# RobotPCB.net
KiCad netlist of a schematic drawn in EAGLE
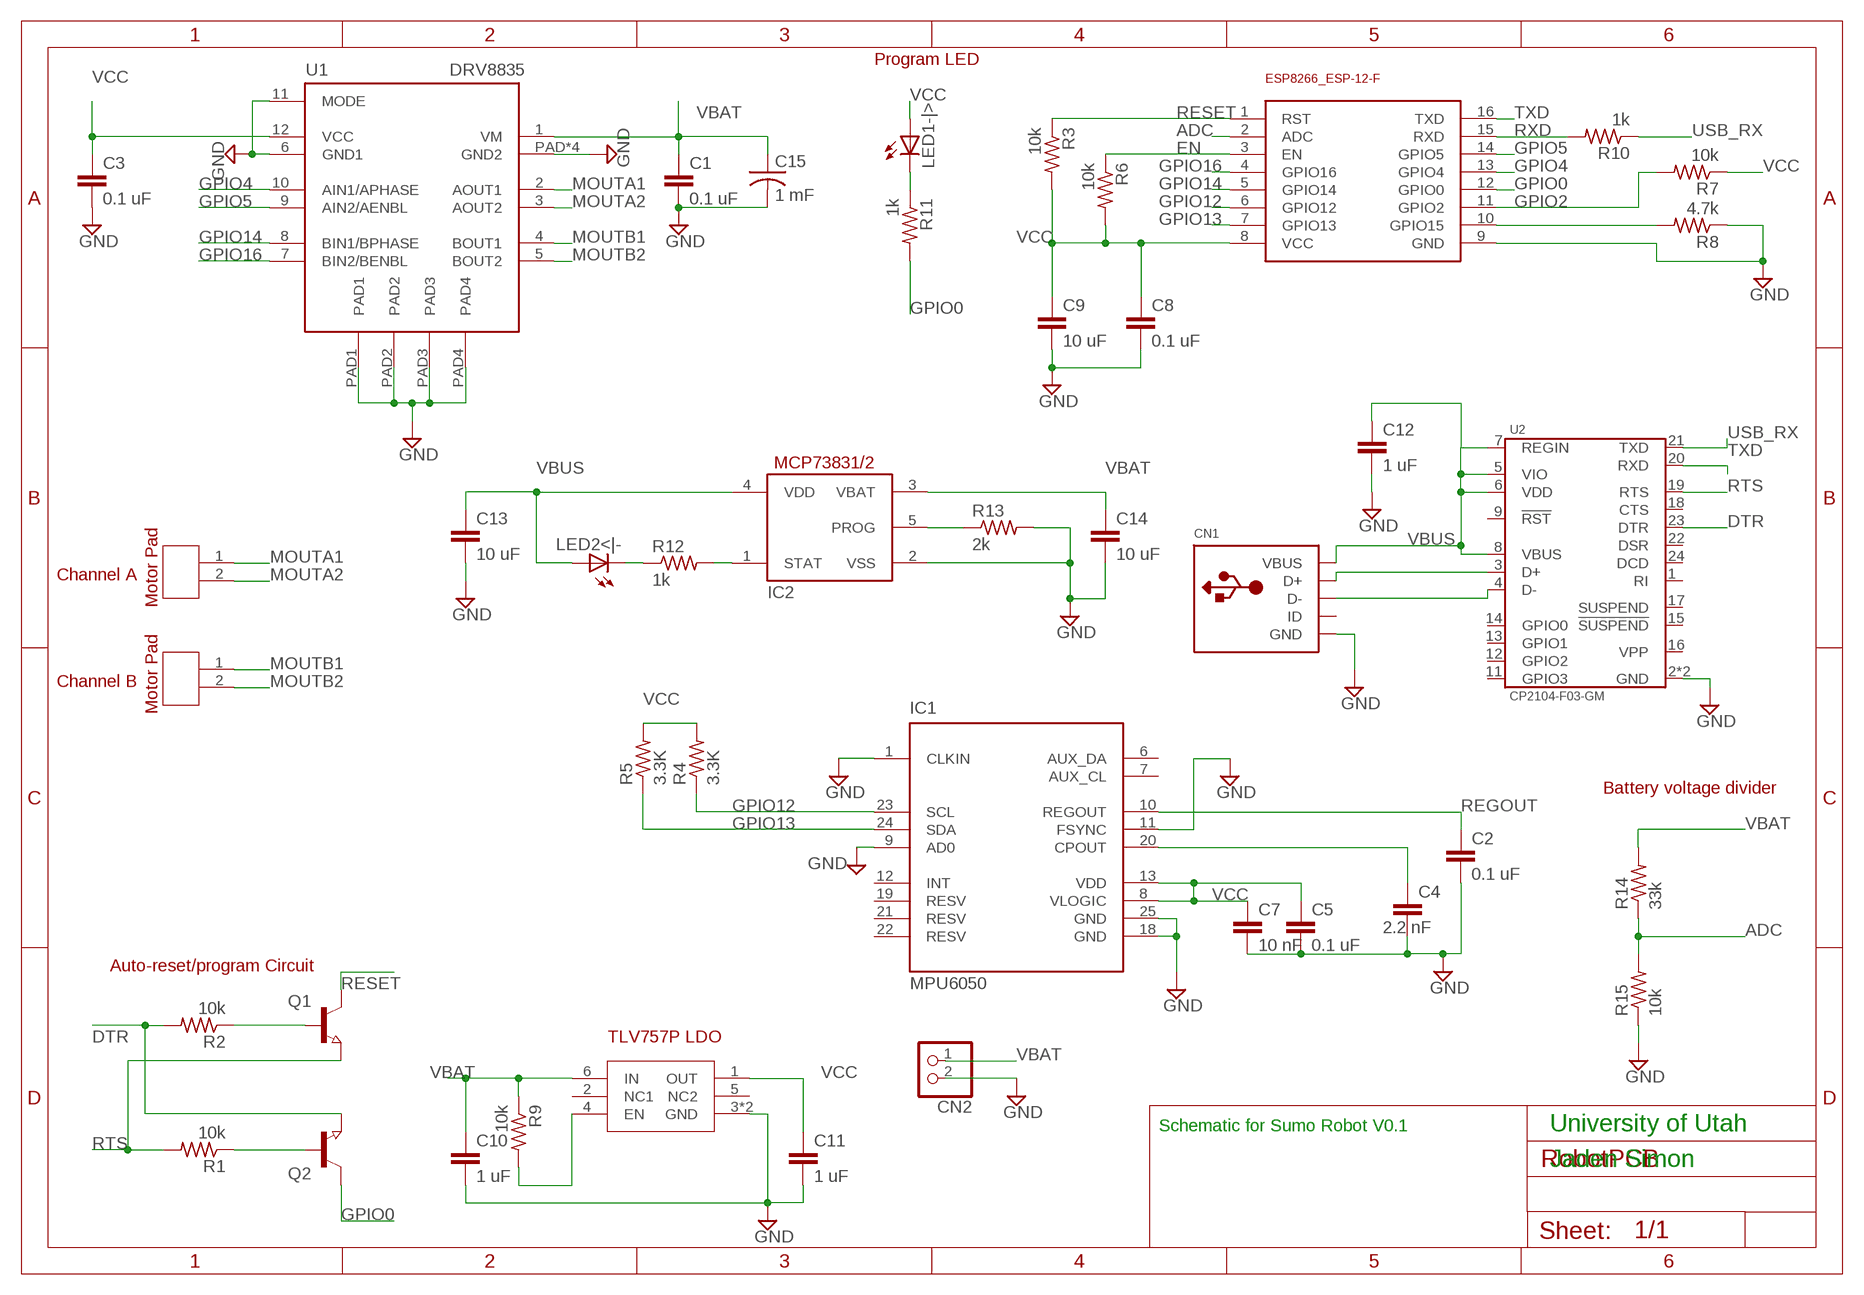
[diagram p0: schematic, sheet 1]

(export (version "E")
  (design (tool "Eeschema 10.0.6"))
  (components
    (comp (ref "C1")
      (value "0.1 uF")
      (footprint "eagle-import:C1206")
      (libsource (lib "eagle-import") (part "C-EUC1206"))
    )
    (comp (ref "C2")
      (value "0.1 uF")
      (footprint "eagle-import:C1206")
      (libsource (lib "eagle-import") (part "C-EUC1206"))
    )
    (comp (ref "C3")
      (value "0.1 uF")
      (footprint "eagle-import:C1206")
      (libsource (lib "eagle-import") (part "C-EUC1206"))
    )
    (comp (ref "C4")
      (value "2.2 nF")
      (footprint "eagle-import:C1206")
      (libsource (lib "eagle-import") (part "C-EUC1206"))
    )
    (comp (ref "C5")
      (value "0.1 uF")
      (footprint "eagle-import:C1206")
      (libsource (lib "eagle-import") (part "C-EUC1206"))
    )
    (comp (ref "C7")
      (value "10 nF")
      (footprint "eagle-import:C1206")
      (libsource (lib "eagle-import") (part "C-EUC1206"))
    )
    (comp (ref "C8")
      (value "0.1 uF")
      (footprint "eagle-import:C1206")
      (libsource (lib "eagle-import") (part "C-EUC1206"))
    )
    (comp (ref "C9")
      (value "10 uF")
      (footprint "eagle-import:C1206")
      (libsource (lib "eagle-import") (part "C-EUC1206"))
    )
    (comp (ref "C10")
      (value "1 uF")
      (footprint "eagle-import:C1206")
      (libsource (lib "eagle-import") (part "C-EUC1206"))
    )
    (comp (ref "C11")
      (value "1 uF")
      (footprint "eagle-import:C1206")
      (libsource (lib "eagle-import") (part "C-EUC1206"))
    )
    (comp (ref "C12")
      (value "1 uF")
      (footprint "eagle-import:C1206")
      (libsource (lib "eagle-import") (part "C-EUC1206"))
    )
    (comp (ref "C13")
      (value "10 uF")
      (footprint "eagle-import:C1206")
      (libsource (lib "eagle-import") (part "C-EUC1206"))
    )
    (comp (ref "C14")
      (value "10 uF")
      (footprint "eagle-import:C1206")
      (libsource (lib "eagle-import") (part "C-EUC1206"))
    )
    (comp (ref "C15")
      (value "1 mF")
      (footprint "eagle-import:C050-075X075")
      (libsource (lib "eagle-import") (part "C-US050-075X075"))
    )
    (comp (ref "CN1")
      (value "USBMINIB")
      (footprint "eagle-import:USB-MINIB")
      (libsource (lib "eagle-import") (part "USBMINIB"))
    )
    (comp (ref "CN2")
      (value "JST_2PIN-THM")
      (footprint "eagle-import:JST-PH-2-THM")
      (libsource (lib "eagle-import") (part "JST_2PIN-THM"))
    )
    (comp (ref "IC1")
      (value "MPU6050")
      (footprint "eagle-import:QFN50P400X400X95-25T265X275N")
      (libsource (lib "eagle-import") (part "MPU6050"))
    )
    (comp (ref "IC2")
      (value "MCP73831/OT")
      (footprint "eagle-import:SOT23-5L")
      (libsource (lib "eagle-import") (part "MCP73831/OT"))
    )
    (comp (ref "LED1-|>")
      (value "LEDSMT1206")
      (footprint "eagle-import:1206")
      (libsource (lib "eagle-import") (part "LEDSMT1206"))
    )
    (comp (ref "LED2<|-")
      (value "LEDSMT1206")
      (footprint "eagle-import:1206")
      (libsource (lib "eagle-import") (part "led_259_LEDSMT1206"))
    )
    (comp (ref "Q1")
      (value "NPN-TRANSISTOR_SOT23")
      (footprint "eagle-import:SOT23")
      (libsource (lib "eagle-import") (part "NPN-TRANSISTOR_SOT23"))
    )
    (comp (ref "Q2")
      (value "NPN-TRANSISTOR_SOT23")
      (footprint "eagle-import:SOT23")
      (libsource (lib "eagle-import") (part "NPN-TRANSISTOR_SOT23"))
    )
    (comp (ref "R1")
      (value "10k")
      (footprint "eagle-import:M1206")
      (libsource (lib "eagle-import") (part "R-US_M1206"))
    )
    (comp (ref "R2")
      (value "10k")
      (footprint "eagle-import:M1206")
      (libsource (lib "eagle-import") (part "R-US_M1206"))
    )
    (comp (ref "R3")
      (value "10k")
      (footprint "eagle-import:M1206")
      (libsource (lib "eagle-import") (part "R-US_M1206"))
    )
    (comp (ref "R4")
      (value "3.3K")
      (footprint "eagle-import:M1206")
      (libsource (lib "eagle-import") (part "R-US_M1206"))
    )
    (comp (ref "R5")
      (value "3.3K")
      (footprint "eagle-import:M1206")
      (libsource (lib "eagle-import") (part "R-US_M1206"))
    )
    (comp (ref "R6")
      (value "10k")
      (footprint "eagle-import:M1206")
      (libsource (lib "eagle-import") (part "R-US_M1206"))
    )
    (comp (ref "R7")
      (value "10k")
      (footprint "eagle-import:M1206")
      (libsource (lib "eagle-import") (part "R-US_M1206"))
    )
    (comp (ref "R8")
      (value "4.7k")
      (footprint "eagle-import:M1206")
      (libsource (lib "eagle-import") (part "R-US_M1206"))
    )
    (comp (ref "R9")
      (value "10k")
      (footprint "eagle-import:M1206")
      (libsource (lib "eagle-import") (part "R-US_M1206"))
    )
    (comp (ref "R10")
      (value "1k")
      (footprint "eagle-import:M1206")
      (libsource (lib "eagle-import") (part "R-US_M1206"))
    )
    (comp (ref "R11")
      (value "1k")
      (footprint "eagle-import:M1206")
      (libsource (lib "eagle-import") (part "R-US_M1206"))
    )
    (comp (ref "R12")
      (value "1k")
      (footprint "eagle-import:M1206")
      (libsource (lib "eagle-import") (part "R-US_M1206"))
    )
    (comp (ref "R13")
      (value "2k")
      (footprint "eagle-import:M1206")
      (libsource (lib "eagle-import") (part "R-US_M1206"))
    )
    (comp (ref "R14")
      (value "33k")
      (footprint "eagle-import:M1206")
      (libsource (lib "eagle-import") (part "R-US_M1206"))
    )
    (comp (ref "R15")
      (value "10k")
      (footprint "eagle-import:M1206")
      (libsource (lib "eagle-import") (part "R-US_M1206"))
    )
    (comp (ref "U$1")
      (value "ESP8266_ESP-12")
      (footprint "eagle-import:ESP8266-ESP12")
      (libsource (lib "eagle-import") (part "ESP8266_ESP-12"))
    )
    (comp (ref "U$2")
      (value "TLV757P")
      (footprint "eagle-import:WSON-6")
      (libsource (lib "eagle-import") (part "TLV757P"))
    )
    (comp (ref "U$3")
      (value "MOTOR_PAD")
      (footprint "eagle-import:MOTOR_PAD")
      (libsource (lib "eagle-import") (part "MOTOR_PAD"))
    )
    (comp (ref "U$4")
      (value "MOTOR_PAD")
      (footprint "eagle-import:MOTOR_PAD")
      (libsource (lib "eagle-import") (part "MOTOR_PAD"))
    )
    (comp (ref "U1")
      (value "DRV8835")
      (footprint "eagle-import:WSON_2X3")
      (libsource (lib "eagle-import") (part "DRV8835"))
    )
    (comp (ref "U2")
      (value "CP2104-F03-GM")
      (footprint "eagle-import:QFN-24-4X4")
      (libsource (lib "eagle-import") (part "CP2104-F03-GM"))
    )
  )
  (nets
    (net (code "1") (name "/ADC") (class "Default")
      (node (ref "R14") (pin "1") (pinfunction "1_1") (pintype "passive"))
      (node (ref "R15") (pin "2") (pinfunction "2_2") (pintype "passive"))
      (node (ref "U$1") (pin "2") (pinfunction "ADC_2") (pintype "bidirectional"))
    )
    (net (code "2") (name "/DTR") (class "Default")
      (node (ref "Q2") (pin "2") (pinfunction "E_2") (pintype "passive"))
      (node (ref "R2") (pin "2") (pinfunction "2_2") (pintype "passive"))
      (node (ref "U2") (pin "23") (pinfunction "DTR_23") (pintype "bidirectional"))
    )
    (net (code "3") (name "/EN") (class "Default")
      (node (ref "R6") (pin "1") (pinfunction "1_1") (pintype "passive"))
      (node (ref "U$1") (pin "3") (pinfunction "EN_3") (pintype "bidirectional"))
    )
    (net (code "4") (name "/GPIO0") (class "Default")
      (node (ref "Q2") (pin "3") (pinfunction "C_3") (pintype "passive"))
      (node (ref "R11") (pin "2") (pinfunction "2_2") (pintype "passive"))
      (node (ref "U$1") (pin "12") (pinfunction "GPIO0_12") (pintype "bidirectional"))
    )
    (net (code "5") (name "/GPIO2") (class "Default")
      (node (ref "R7") (pin "2") (pinfunction "2_2") (pintype "passive"))
      (node (ref "U$1") (pin "11") (pinfunction "GPIO2_11") (pintype "bidirectional"))
    )
    (net (code "6") (name "/GPIO4") (class "Default")
      (node (ref "U$1") (pin "13") (pinfunction "GPIO4_13") (pintype "bidirectional"))
      (node (ref "U1") (pin "10") (pinfunction "AIN1/APHASE_10") (pintype "bidirectional"))
    )
    (net (code "7") (name "/GPIO5") (class "Default")
      (node (ref "U$1") (pin "14") (pinfunction "GPIO5_14") (pintype "bidirectional"))
      (node (ref "U1") (pin "9") (pinfunction "AIN2/AENBL_9") (pintype "bidirectional"))
    )
    (net (code "8") (name "/GPIO12") (class "Default")
      (node (ref "IC1") (pin "23") (pinfunction "SCL_23") (pintype "input"))
      (node (ref "R4") (pin "1") (pinfunction "1_1") (pintype "passive"))
      (node (ref "U$1") (pin "6") (pinfunction "GPIO12_6") (pintype "bidirectional"))
    )
    (net (code "9") (name "/GPIO13") (class "Default")
      (node (ref "IC1") (pin "24") (pinfunction "SDA_24") (pintype "bidirectional"))
      (node (ref "R5") (pin "1") (pinfunction "1_1") (pintype "passive"))
      (node (ref "U$1") (pin "7") (pinfunction "GPIO13_7") (pintype "bidirectional"))
    )
    (net (code "10") (name "/GPIO14") (class "Default")
      (node (ref "U$1") (pin "5") (pinfunction "GPIO14_5") (pintype "bidirectional"))
      (node (ref "U1") (pin "8") (pinfunction "BIN1/BPHASE_8") (pintype "bidirectional"))
    )
    (net (code "11") (name "/GPIO16") (class "Default")
      (node (ref "U$1") (pin "4") (pinfunction "GPIO16_4") (pintype "bidirectional"))
      (node (ref "U1") (pin "7") (pinfunction "BIN2/BENBL_7") (pintype "bidirectional"))
    )
    (net (code "12") (name "/MOUTA1") (class "Default")
      (node (ref "U$3") (pin "1") (pinfunction "L_1") (pintype "input"))
      (node (ref "U1") (pin "2") (pinfunction "AOUT1_2") (pintype "bidirectional"))
    )
    (net (code "13") (name "/MOUTA2") (class "Default")
      (node (ref "U$3") (pin "2") (pinfunction "2_2") (pintype "input"))
      (node (ref "U1") (pin "3") (pinfunction "AOUT2_3") (pintype "bidirectional"))
    )
    (net (code "14") (name "/MOUTB1") (class "Default")
      (node (ref "U$4") (pin "1") (pinfunction "L_1") (pintype "input"))
      (node (ref "U1") (pin "4") (pinfunction "BOUT1_4") (pintype "bidirectional"))
    )
    (net (code "15") (name "/MOUTB2") (class "Default")
      (node (ref "U$4") (pin "2") (pinfunction "2_2") (pintype "input"))
      (node (ref "U1") (pin "5") (pinfunction "BOUT2_5") (pintype "bidirectional"))
    )
    (net (code "16") (name "/REGOUT") (class "Default")
      (node (ref "C2") (pin "1") (pinfunction "1_1") (pintype "passive"))
      (node (ref "IC1") (pin "10") (pinfunction "REGOUT_10") (pintype "output"))
    )
    (net (code "17") (name "/RESET") (class "Default")
      (node (ref "Q1") (pin "3") (pinfunction "C_3") (pintype "passive"))
      (node (ref "R3") (pin "1") (pinfunction "1_1") (pintype "passive"))
      (node (ref "U$1") (pin "1") (pinfunction "RST_1") (pintype "bidirectional"))
    )
    (net (code "18") (name "/RTS") (class "Default")
      (node (ref "Q1") (pin "2") (pinfunction "E_2") (pintype "passive"))
      (node (ref "R1") (pin "2") (pinfunction "2_2") (pintype "passive"))
      (node (ref "U2") (pin "19") (pinfunction "RTS_19") (pintype "bidirectional"))
    )
    (net (code "19") (name "/RXD") (class "Default")
      (node (ref "R10") (pin "2") (pinfunction "2_2") (pintype "passive"))
      (node (ref "U$1") (pin "15") (pinfunction "RXD_15") (pintype "bidirectional"))
    )
    (net (code "20") (name "/TXD") (class "Default")
      (node (ref "U$1") (pin "16") (pinfunction "TXD_16") (pintype "bidirectional"))
      (node (ref "U2") (pin "20") (pinfunction "RXD_20") (pintype "bidirectional"))
    )
    (net (code "21") (name "/USB_RX") (class "Default")
      (node (ref "R10") (pin "1") (pinfunction "1_1") (pintype "passive"))
      (node (ref "U2") (pin "21") (pinfunction "TXD_21") (pintype "bidirectional"))
    )
    (net (code "22") (name "/VBAT") (class "Default")
      (node (ref "C1") (pin "1") (pinfunction "1_1") (pintype "passive"))
      (node (ref "C10") (pin "1") (pinfunction "1_1") (pintype "passive"))
      (node (ref "C14") (pin "1") (pinfunction "1_1") (pintype "passive"))
      (node (ref "C15") (pin "1") (pinfunction "1_1") (pintype "passive"))
      (node (ref "CN2") (pin "1") (pinfunction "2_1") (pintype "passive"))
      (node (ref "IC2") (pin "3") (pinfunction "VBAT_3") (pintype "bidirectional"))
      (node (ref "R14") (pin "2") (pinfunction "2_2") (pintype "passive"))
      (node (ref "R9") (pin "1") (pinfunction "1_1") (pintype "passive"))
      (node (ref "U$2") (pin "6") (pinfunction "IN_6") (pintype "bidirectional"))
      (node (ref "U1") (pin "1") (pinfunction "VM_1") (pintype "bidirectional"))
    )
    (net (code "23") (name "/VBUS") (class "Default")
      (node (ref "C12") (pin "1") (pinfunction "1_1") (pintype "passive"))
      (node (ref "C13") (pin "1") (pinfunction "1_1") (pintype "passive"))
      (node (ref "CN1") (pin "VBUS") (pinfunction "VBUS_VBUS") (pintype "power_in"))
      (node (ref "IC2") (pin "4") (pinfunction "VDD_4") (pintype "power_in"))
      (node (ref "LED2<|-") (pin "A") (pinfunction "A_A") (pintype "passive"))
      (node (ref "U2") (pin "5") (pinfunction "VIO_5") (pintype "bidirectional"))
      (node (ref "U2") (pin "6") (pinfunction "VDD_6") (pintype "bidirectional"))
      (node (ref "U2") (pin "7") (pinfunction "REGIN_7") (pintype "bidirectional"))
      (node (ref "U2") (pin "8") (pinfunction "VBUS_8") (pintype "bidirectional"))
    )
    (net (code "24") (name "/VCC") (class "Default")
      (node (ref "C11") (pin "1") (pinfunction "1_1") (pintype "passive"))
      (node (ref "C3") (pin "1") (pinfunction "1_1") (pintype "passive"))
      (node (ref "C5") (pin "1") (pinfunction "1_1") (pintype "passive"))
      (node (ref "C7") (pin "1") (pinfunction "1_1") (pintype "passive"))
      (node (ref "C8") (pin "1") (pinfunction "1_1") (pintype "passive"))
      (node (ref "C9") (pin "1") (pinfunction "1_1") (pintype "passive"))
      (node (ref "IC1") (pin "13") (pinfunction "VDD_13") (pintype "power_in"))
      (node (ref "IC1") (pin "8") (pinfunction "VLOGIC_8") (pintype "power_in"))
      (node (ref "LED1-|>") (pin "A") (pinfunction "A_A") (pintype "passive"))
      (node (ref "R3") (pin "2") (pinfunction "2_2") (pintype "passive"))
      (node (ref "R4") (pin "2") (pinfunction "2_2") (pintype "passive"))
      (node (ref "R5") (pin "2") (pinfunction "2_2") (pintype "passive"))
      (node (ref "R6") (pin "2") (pinfunction "2_2") (pintype "passive"))
      (node (ref "R7") (pin "1") (pinfunction "1_1") (pintype "passive"))
      (node (ref "U$1") (pin "8") (pinfunction "VCC_8") (pintype "bidirectional"))
      (node (ref "U$2") (pin "1") (pinfunction "OUT_1") (pintype "bidirectional"))
      (node (ref "U1") (pin "12") (pinfunction "VCC_12") (pintype "bidirectional"))
    )
    (net (code "25") (name "GND") (class "Default")
      (node (ref "C1") (pin "2") (pinfunction "2_2") (pintype "passive"))
      (node (ref "C10") (pin "2") (pinfunction "2_2") (pintype "passive"))
      (node (ref "C11") (pin "2") (pinfunction "2_2") (pintype "passive"))
      (node (ref "C12") (pin "2") (pinfunction "2_2") (pintype "passive"))
      (node (ref "C13") (pin "2") (pinfunction "2_2") (pintype "passive"))
      (node (ref "C14") (pin "2") (pinfunction "2_2") (pintype "passive"))
      (node (ref "C15") (pin "2") (pinfunction "2_2") (pintype "passive"))
      (node (ref "C2") (pin "2") (pinfunction "2_2") (pintype "passive"))
      (node (ref "C3") (pin "2") (pinfunction "2_2") (pintype "passive"))
      (node (ref "C4") (pin "2") (pinfunction "2_2") (pintype "passive"))
      (node (ref "C5") (pin "2") (pinfunction "2_2") (pintype "passive"))
      (node (ref "C7") (pin "2") (pinfunction "2_2") (pintype "passive"))
      (node (ref "C8") (pin "2") (pinfunction "2_2") (pintype "passive"))
      (node (ref "C9") (pin "2") (pinfunction "2_2") (pintype "passive"))
      (node (ref "CN1") (pin "GND") (pinfunction "GND_GND") (pintype "power_in"))
      (node (ref "CN2") (pin "2") (pinfunction "1_2") (pintype "passive"))
      (node (ref "IC1") (pin "1") (pinfunction "CLKIN_1") (pintype "input"))
      (node (ref "IC1") (pin "11") (pinfunction "FSYNC_11") (pintype "input"))
      (node (ref "IC1") (pin "18") (pinfunction "GND_18") (pintype "power_in"))
      (node (ref "IC1") (pin "25") (pinfunction "GND_25") (pintype "power_in"))
      (node (ref "IC1") (pin "9") (pinfunction "AD0_9") (pintype "input"))
      (node (ref "IC2") (pin "2") (pinfunction "VSS_2") (pintype "power_in"))
      (node (ref "R13") (pin "2") (pinfunction "2_2") (pintype "passive"))
      (node (ref "R15") (pin "1") (pinfunction "1_1") (pintype "passive"))
      (node (ref "R8") (pin "1") (pinfunction "1_1") (pintype "passive"))
      (node (ref "U$1") (pin "9") (pinfunction "GND_9") (pintype "bidirectional"))
      (node (ref "U$2") (pin "3") (pinfunction "GND_3") (pintype "bidirectional"))
      (node (ref "U$2") (pin "7") (pinfunction "GND_7") (pintype "bidirectional"))
      (node (ref "U1") (pin "11") (pinfunction "MODE_11") (pintype "bidirectional"))
      (node (ref "U1") (pin "6") (pinfunction "GND1_6") (pintype "bidirectional"))
      (node (ref "U1") (pin "PAD") (pinfunction "GND2_PAD") (pintype "bidirectional"))
      (node (ref "U1") (pin "PAD1") (pinfunction "PAD1_PAD1") (pintype "bidirectional"))
      (node (ref "U1") (pin "PAD2") (pinfunction "PAD2_PAD2") (pintype "bidirectional"))
      (node (ref "U1") (pin "PAD3") (pinfunction "PAD3_PAD3") (pintype "bidirectional"))
      (node (ref "U1") (pin "PAD4") (pinfunction "PAD4_PAD4") (pintype "bidirectional"))
      (node (ref "U1") (pin "PAD5") (pinfunction "GND2_PAD5") (pintype "bidirectional"))
      (node (ref "U1") (pin "PAD6") (pinfunction "GND2_PAD6") (pintype "bidirectional"))
      (node (ref "U1") (pin "PAD7") (pinfunction "GND2_PAD7") (pintype "bidirectional"))
      (node (ref "U2") (pin "2") (pinfunction "GND_2") (pintype "bidirectional"))
      (node (ref "U2") (pin "PAD") (pinfunction "GND_PAD") (pintype "bidirectional"))
    )
    (net (code "26") (name "Net-(IC1A-CPOUT)") (class "Default")
      (node (ref "C4") (pin "1") (pinfunction "1_1") (pintype "passive"))
      (node (ref "IC1") (pin "20") (pinfunction "CPOUT_20") (pintype "output"))
    )
    (net (code "27") (name "Net-(IC2-PROG)") (class "Default")
      (node (ref "IC2") (pin "5") (pinfunction "PROG_5") (pintype "input"))
      (node (ref "R13") (pin "1") (pinfunction "1_1") (pintype "passive"))
    )
    (net (code "28") (name "Net-(IC2-STAT)") (class "Default")
      (node (ref "IC2") (pin "1") (pinfunction "STAT_1") (pintype "output"))
      (node (ref "R12") (pin "2") (pinfunction "2_2") (pintype "passive"))
    )
    (net (code "29") (name "Net-(LED1-|>-PadC)") (class "Default")
      (node (ref "LED1-|>") (pin "C") (pinfunction "C_C") (pintype "passive"))
      (node (ref "R11") (pin "1") (pinfunction "1_1") (pintype "passive"))
    )
    (net (code "30") (name "Net-(LED2<|--PadC)") (class "Default")
      (node (ref "LED2<|-") (pin "C") (pinfunction "C_C") (pintype "passive"))
      (node (ref "R12") (pin "1") (pinfunction "1_1") (pintype "passive"))
    )
    (net (code "31") (name "Net-(Q1-B)") (class "Default")
      (node (ref "Q1") (pin "1") (pinfunction "B_1") (pintype "passive"))
      (node (ref "R2") (pin "1") (pinfunction "1_1") (pintype "passive"))
    )
    (net (code "32") (name "Net-(Q2-B)") (class "Default")
      (node (ref "Q2") (pin "1") (pinfunction "B_1") (pintype "passive"))
      (node (ref "R1") (pin "1") (pinfunction "1_1") (pintype "passive"))
    )
    (net (code "33") (name "Net-(U$1-GPIO15)") (class "Default")
      (node (ref "R8") (pin "2") (pinfunction "2_2") (pintype "passive"))
      (node (ref "U$1") (pin "10") (pinfunction "GPIO15_10") (pintype "bidirectional"))
    )
    (net (code "34") (name "Net-(U$2-EN)") (class "Default")
      (node (ref "R9") (pin "2") (pinfunction "2_2") (pintype "passive"))
      (node (ref "U$2") (pin "4") (pinfunction "EN_4") (pintype "bidirectional"))
    )
    (net (code "35") (name "Net-(U2-D+)") (class "Default")
      (node (ref "CN1") (pin "D+") (pinfunction "D+_D+") (pintype "bidirectional"))
      (node (ref "U2") (pin "3") (pinfunction "D+_3") (pintype "bidirectional"))
    )
    (net (code "36") (name "Net-(U2-D-)") (class "Default")
      (node (ref "CN1") (pin "D-") (pinfunction "D-_D-") (pintype "bidirectional"))
      (node (ref "U2") (pin "4") (pinfunction "D-_4") (pintype "bidirectional"))
    )
    (net (code "37") (name "unconnected-(CN1-PadID)") (class "Default")
      (node (ref "CN1") (pin "ID") (pinfunction "ID_ID") (pintype "bidirectional"))
    )
    (net (code "38") (name "unconnected-(IC1A-AUX_CL-Pad7)") (class "Default")
      (node (ref "IC1") (pin "7") (pinfunction "AUX_CL_7") (pintype "bidirectional"))
    )
    (net (code "39") (name "unconnected-(IC1A-AUX_DA-Pad6)") (class "Default")
      (node (ref "IC1") (pin "6") (pinfunction "AUX_DA_6") (pintype "bidirectional"))
    )
    (net (code "40") (name "unconnected-(IC1A-INT-Pad12)") (class "Default")
      (node (ref "IC1") (pin "12") (pinfunction "INT_12") (pintype "open_collector"))
    )
    (net (code "41") (name "unconnected-(IC1A-RESV-Pad19)") (class "Default")
      (node (ref "IC1") (pin "19") (pinfunction "RESV_19") (pintype "passive"))
    )
    (net (code "42") (name "unconnected-(IC1A-RESV-Pad21)") (class "Default")
      (node (ref "IC1") (pin "21") (pinfunction "RESV_21") (pintype "passive"))
    )
    (net (code "43") (name "unconnected-(IC1A-RESV-Pad22)") (class "Default")
      (node (ref "IC1") (pin "22") (pinfunction "RESV_22") (pintype "passive"))
    )
    (net (code "44") (name "unconnected-(U$2-NC1-Pad2)") (class "Default")
      (node (ref "U$2") (pin "2") (pinfunction "NC1_2") (pintype "bidirectional"))
    )
    (net (code "45") (name "unconnected-(U$2-NC2-Pad5)") (class "Default")
      (node (ref "U$2") (pin "5") (pinfunction "NC2_5") (pintype "bidirectional"))
    )
    (net (code "46") (name "unconnected-(U2-CTS-Pad18)") (class "Default")
      (node (ref "U2") (pin "18") (pinfunction "CTS_18") (pintype "bidirectional"))
    )
    (net (code "47") (name "unconnected-(U2-DCD-Pad24)") (class "Default")
      (node (ref "U2") (pin "24") (pinfunction "DCD_24") (pintype "bidirectional"))
    )
    (net (code "48") (name "unconnected-(U2-DSR-Pad22)") (class "Default")
      (node (ref "U2") (pin "22") (pinfunction "DSR_22") (pintype "bidirectional"))
    )
    (net (code "49") (name "unconnected-(U2-GPIO0-Pad14)") (class "Default")
      (node (ref "U2") (pin "14") (pinfunction "GPIO0_14") (pintype "bidirectional"))
    )
    (net (code "50") (name "unconnected-(U2-GPIO1-Pad13)") (class "Default")
      (node (ref "U2") (pin "13") (pinfunction "GPIO1_13") (pintype "bidirectional"))
    )
    (net (code "51") (name "unconnected-(U2-GPIO2-Pad12)") (class "Default")
      (node (ref "U2") (pin "12") (pinfunction "GPIO2_12") (pintype "bidirectional"))
    )
    (net (code "52") (name "unconnected-(U2-GPIO3-Pad11)") (class "Default")
      (node (ref "U2") (pin "11") (pinfunction "GPIO3_11") (pintype "bidirectional"))
    )
    (net (code "53") (name "unconnected-(U2-RI-Pad1)") (class "Default")
      (node (ref "U2") (pin "1") (pinfunction "RI_1") (pintype "bidirectional"))
    )
    (net (code "54") (name "unconnected-(U2-SUSPEND-Pad17)") (class "Default")
      (node (ref "U2") (pin "17") (pinfunction "SUSPEND_17") (pintype "bidirectional"))
    )
    (net (code "55") (name "unconnected-(U2-VPP-Pad16)") (class "Default")
      (node (ref "U2") (pin "16") (pinfunction "VPP_16") (pintype "bidirectional"))
    )
    (net (code "56") (name "unconnected-(U2-~{RST}-Pad9)") (class "Default")
      (node (ref "U2") (pin "9") (pinfunction "~{RST}_9") (pintype "bidirectional"))
    )
    (net (code "57") (name "unconnected-(U2-~{SUSPEND}-Pad15)") (class "Default")
      (node (ref "U2") (pin "15") (pinfunction "~{SUSPEND}_15") (pintype "bidirectional"))
    )
  )
)
